# design.net
KiCad netlist of a schematic drawn in Altium Designer
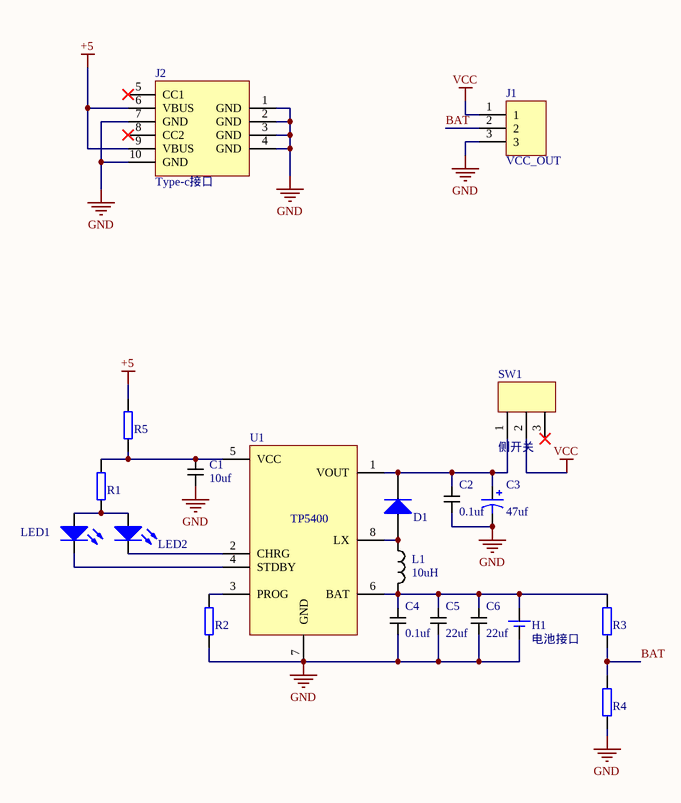
[diagram p0: 电源小板.SchDoc]

(export (version "E")
  (design (tool "Eeschema 10.0.6"))
  (components
    (comp (ref "C1")
      (value "10uf")
      (footprint "0603-CAP")
      (description "无极性贴片电容")
      (libsource (lib "定位手表") (part "电容"))
    )
    (comp (ref "C2")
      (value "0.1uf")
      (footprint "0603-CAP")
      (description "无极性贴片电容")
      (libsource (lib "定位手表") (part "电容"))
    )
    (comp (ref "C3")
      (value "47uf")
      (footprint "电解电容")
      (description "极性直插电容")
      (libsource (lib "定位手表") (part "极性电容"))
    )
    (comp (ref "C4")
      (value "0.1uf")
      (footprint "0603-CAP")
      (description "无极性贴片电容")
      (libsource (lib "定位手表") (part "电容"))
    )
    (comp (ref "C5")
      (value "22uf")
      (footprint "0603-CAP")
      (description "无极性贴片电容")
      (libsource (lib "定位手表") (part "电容"))
    )
    (comp (ref "C6")
      (value "22uf")
      (footprint "0603-CAP")
      (description "无极性贴片电容")
      (libsource (lib "定位手表") (part "电容"))
    )
    (comp (ref "D1")
      (value "二极管")
      (footprint "DO-214AC")
      (description "通用二极管")
      (libsource (lib "定位手表") (part "二极管"))
    )
    (comp (ref "H1")
      (value "电池接口")
      (footprint "PH2.0")
      (description "接电池用的")
      (libsource (lib "定位手表") (part "电池接口"))
    )
    (comp (ref "J1") (value "VCC_OUT") (footprint "ZH1.5") (libsource (lib "定位手表") (part "VCC_OUT")))
    (comp (ref "J2")
      (value "Type-c接口")
      (footprint "type-c")
      (description "接口")
      (libsource (lib "定位手表") (part "Type-c接口"))
    )
    (comp (ref "L1")
      (value "10uH")
      (footprint "功率电感")
      (description "普通电感")
      (fields (field (name "PUBLISHER") "Altium Limited"))
      (libsource (lib "定位手表") (part "电感"))
    )
    (comp (ref "LED1") (value "发光二极管") (footprint "0603-LED") (libsource (lib "定位手表") (part "发光二极管")))
    (comp (ref "LED2") (value "发光二极管") (footprint "0603-LED") (libsource (lib "定位手表") (part "发光二极管")))
    (comp (ref "R1") (value "电阻") (footprint "0603-RES") (libsource (lib "定位手表") (part "电阻")))
    (comp (ref "R2") (value "电阻") (footprint "0603-RES") (libsource (lib "定位手表") (part "电阻")))
    (comp (ref "R3") (value "电阻") (footprint "0603-RES") (libsource (lib "定位手表") (part "电阻")))
    (comp (ref "R4") (value "电阻") (footprint "0603-RES") (libsource (lib "定位手表") (part "电阻")))
    (comp (ref "R5") (value "电阻") (footprint "0603-RES") (libsource (lib "定位手表") (part "电阻")))
    (comp (ref "SW1") (value "侧开关") (footprint "开关") (libsource (lib "定位手表") (part "侧开关")))
    (comp (ref "U1")
      (value "TP5400")
      (footprint "TP5400")
      (description "电源管理芯片")
      (libsource (lib "定位手表") (part "TP5400"))
    )
  )
  (nets
    (net (code "1") (name "+5") (class "Default")
      (node (ref "J2") (pin "6") (pinfunction "VBUS_6") (pintype "passive"))
      (node (ref "J2") (pin "9") (pinfunction "VBUS_9") (pintype "passive"))
      (node (ref "R5") (pin "1") (pinfunction "1_1") (pintype "passive"))
    )
    (net (code "2") (name "/BAT") (class "Default")
      (node (ref "J1") (pin "2") (pinfunction "2_2") (pintype "passive"))
      (node (ref "R3") (pin "2") (pinfunction "2_2") (pintype "passive"))
      (node (ref "R4") (pin "1") (pinfunction "1_1") (pintype "passive"))
    )
    (net (code "3") (name "GND") (class "Default")
      (node (ref "C1") (pin "2") (pintype "passive"))
      (node (ref "C2") (pin "2") (pintype "passive"))
      (node (ref "C3") (pin "2") (pinfunction "2_2") (pintype "passive"))
      (node (ref "C4") (pin "2") (pintype "passive"))
      (node (ref "C5") (pin "2") (pintype "passive"))
      (node (ref "C6") (pin "2") (pintype "passive"))
      (node (ref "H1") (pin "2") (pinfunction "负极_2") (pintype "passive"))
      (node (ref "J1") (pin "3") (pinfunction "3_3") (pintype "passive"))
      (node (ref "J2") (pin "1") (pinfunction "GND_1") (pintype "passive"))
      (node (ref "J2") (pin "10") (pinfunction "GND_10") (pintype "passive"))
      (node (ref "J2") (pin "2") (pinfunction "GND_2") (pintype "passive"))
      (node (ref "J2") (pin "3") (pinfunction "GND_3") (pintype "passive"))
      (node (ref "J2") (pin "4") (pinfunction "GND_4") (pintype "passive"))
      (node (ref "J2") (pin "7") (pinfunction "GND_7") (pintype "passive"))
      (node (ref "R2") (pin "2") (pinfunction "2_2") (pintype "passive"))
      (node (ref "R4") (pin "2") (pinfunction "2_2") (pintype "passive"))
      (node (ref "U1") (pin "7") (pinfunction "GND_7") (pintype "passive"))
    )
    (net (code "4") (name "Net-(D1-A)") (class "Default")
      (node (ref "D1") (pin "1") (pinfunction "A_1") (pintype "passive"))
      (node (ref "L1") (pin "1") (pinfunction "1_1") (pintype "passive"))
      (node (ref "U1") (pin "8") (pinfunction "LX_8") (pintype "passive"))
    )
    (net (code "5") (name "Net-(D1-K)") (class "Default")
      (node (ref "C2") (pin "1") (pintype "passive"))
      (node (ref "C3") (pin "1") (pinfunction "1_1") (pintype "passive"))
      (node (ref "D1") (pin "2") (pinfunction "K_2") (pintype "passive"))
      (node (ref "SW1") (pin "1") (pinfunction "1_1") (pintype "passive"))
      (node (ref "U1") (pin "1") (pinfunction "VOUT_1") (pintype "passive"))
    )
    (net (code "6") (name "Net-(H1-正极)") (class "Default")
      (node (ref "C4") (pin "1") (pintype "passive"))
      (node (ref "C5") (pin "1") (pintype "passive"))
      (node (ref "C6") (pin "1") (pintype "passive"))
      (node (ref "H1") (pin "1") (pinfunction "正极_1") (pintype "passive"))
      (node (ref "L1") (pin "2") (pinfunction "2_2") (pintype "passive"))
      (node (ref "R3") (pin "1") (pinfunction "1_1") (pintype "passive"))
      (node (ref "U1") (pin "6") (pinfunction "BAT_6") (pintype "passive"))
    )
    (net (code "7") (name "Net-(LED1-Pad1)") (class "Default")
      (node (ref "LED1") (pin "1") (pinfunction "1_1") (pintype "passive"))
      (node (ref "LED2") (pin "1") (pinfunction "1_1") (pintype "passive"))
      (node (ref "R1") (pin "2") (pinfunction "2_2") (pintype "passive"))
    )
    (net (code "8") (name "Net-(U1-CHRG)") (class "Default")
      (node (ref "LED2") (pin "2") (pinfunction "2_2") (pintype "passive"))
      (node (ref "U1") (pin "2") (pinfunction "CHRG_2") (pintype "passive"))
    )
    (net (code "9") (name "Net-(U1-PROG)") (class "Default")
      (node (ref "R2") (pin "1") (pinfunction "1_1") (pintype "passive"))
      (node (ref "U1") (pin "3") (pinfunction "PROG_3") (pintype "passive"))
    )
    (net (code "10") (name "Net-(U1-STDBY)") (class "Default")
      (node (ref "LED1") (pin "2") (pinfunction "2_2") (pintype "passive"))
      (node (ref "U1") (pin "4") (pinfunction "STDBY_4") (pintype "passive"))
    )
    (net (code "11") (name "Net-(U1-VCC)") (class "Default")
      (node (ref "C1") (pin "1") (pintype "passive"))
      (node (ref "R1") (pin "1") (pinfunction "1_1") (pintype "passive"))
      (node (ref "R5") (pin "2") (pinfunction "2_2") (pintype "passive"))
      (node (ref "U1") (pin "5") (pinfunction "VCC_5") (pintype "passive"))
    )
    (net (code "12") (name "VCC") (class "Default")
      (node (ref "J1") (pin "1") (pinfunction "1_1") (pintype "passive"))
      (node (ref "SW1") (pin "2") (pinfunction "2_2") (pintype "passive"))
    )
    (net (code "13") (name "unconnected-(J2-CC1-Pad5)") (class "Default")
      (node (ref "J2") (pin "5") (pinfunction "CC1_5") (pintype "passive+no_connect"))
    )
    (net (code "14") (name "unconnected-(J2-CC2-Pad8)") (class "Default")
      (node (ref "J2") (pin "8") (pinfunction "CC2_8") (pintype "passive+no_connect"))
    )
    (net (code "15") (name "unconnected-(SW1-Pad3)") (class "Default")
      (node (ref "SW1") (pin "3") (pinfunction "3_3") (pintype "passive+no_connect"))
    )
  )
)
